# OTP5.net
KiCad netlist of a schematic drawn in Altium Designer
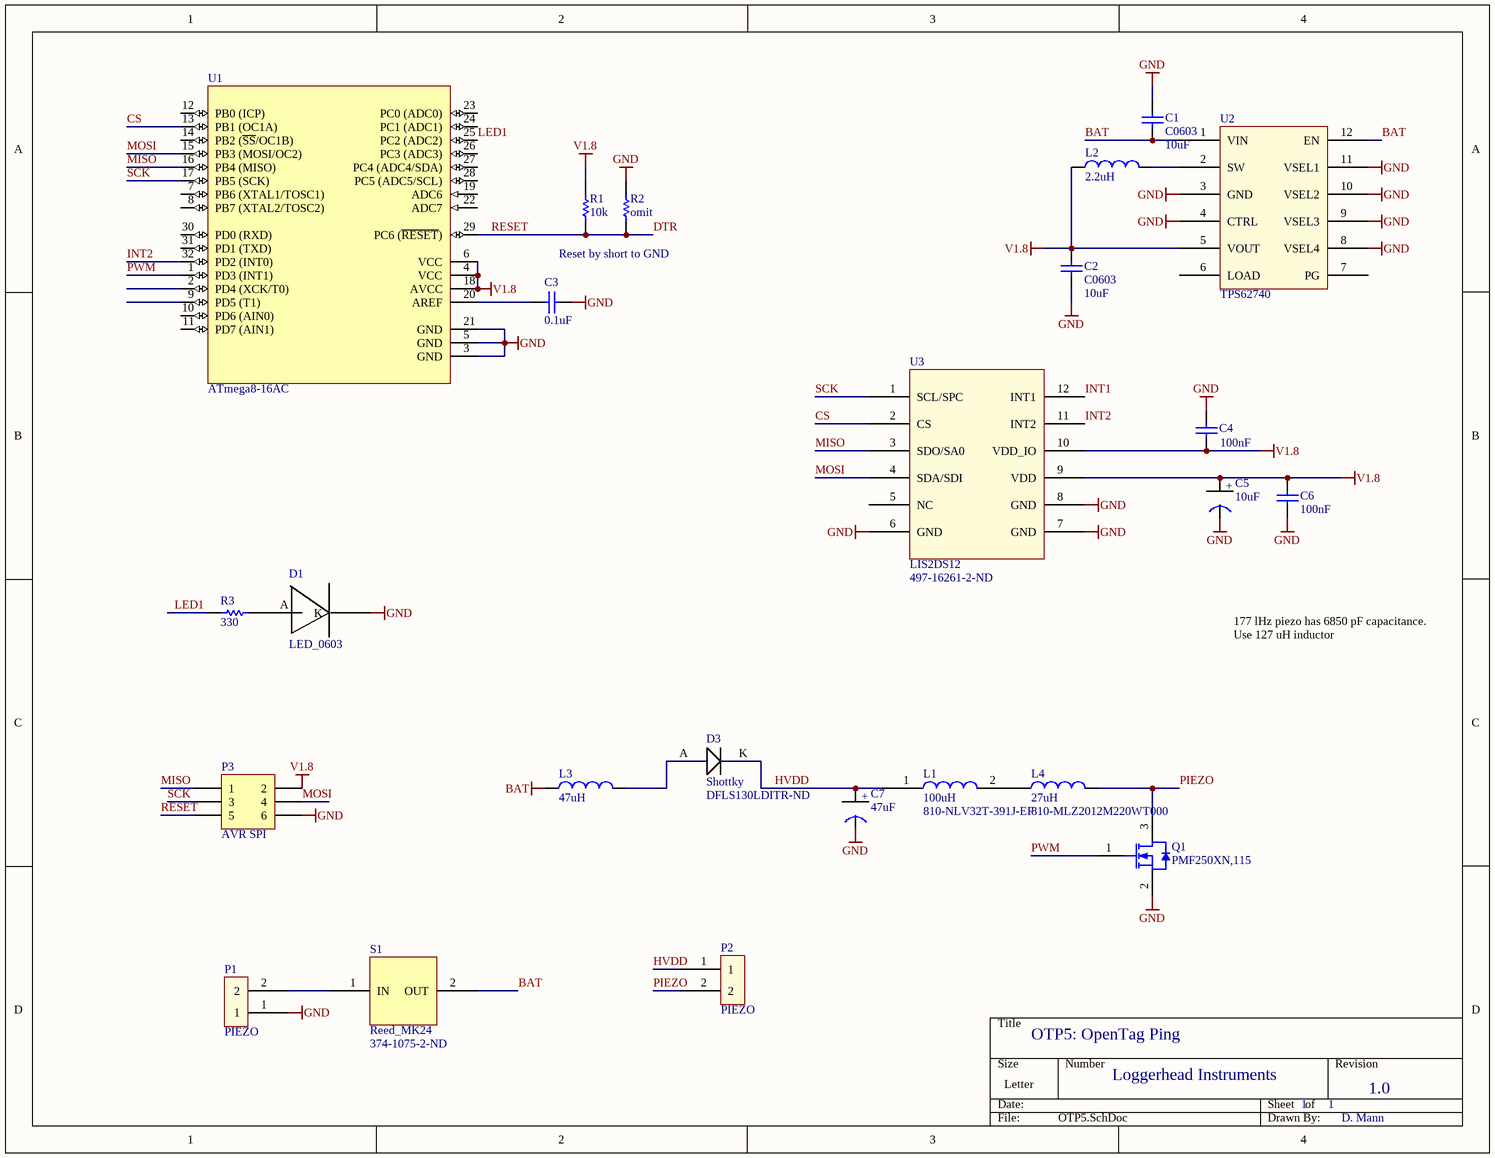
[diagram p0: OTP5.SchDoc]

(export (version "E")
  (design (tool "Eeschema 10.0.6"))
  (components
    (comp (ref "C1")
      (value "C0603")
      (footprint "0603")
      (description "Ceramic Chip Capacitor - Standard")
      (fields (field (name "ALTIUM_VALUE") "10uF") (field (name "PUBLISHER") "Altium Limited"))
      (libsource (lib "KEMET Chip Capacitor") (part "C0603"))
    )
    (comp (ref "C2")
      (value "C0603")
      (footprint "0603")
      (description "Ceramic Chip Capacitor - Standard")
      (fields (field (name "ALTIUM_VALUE") "10uF") (field (name "PUBLISHER") "Altium Limited"))
      (libsource (lib "KEMET Chip Capacitor") (part "C0603"))
    )
    (comp (ref "C3")
      (value "0.1uF")
      (footprint "0402")
      (description "Ceramic Chip Capacitor - Standard")
      (fields (field (name "PUBLISHER") "Altium Limited"))
      (libsource (lib "KEMET Chip Capacitor") (part "C0402"))
    )
    (comp (ref "C4")
      (value "100nF")
      (footprint "0402")
      (description "Ceramic Chip Capacitor - Standard")
      (fields (field (name "PUBLISHER") "Altium Limited"))
      (libsource (lib "KEMET Chip Capacitor") (part "C0402"))
    )
    (comp (ref "C5") (value "10uF") (footprint "Tant0805") (libsource (lib "Loggerhead") (part "Tant0805")))
    (comp (ref "C6")
      (value "100nF")
      (footprint "0402")
      (description "Ceramic Chip Capacitor - Standard")
      (fields (field (name "PUBLISHER") "Altium Limited"))
      (libsource (lib "KEMET Chip Capacitor") (part "C0402"))
    )
    (comp (ref "C7") (value "47uF") (footprint "Tant0805") (libsource (lib "Loggerhead") (part "Tant0805")))
    (comp (ref "D1")
      (value "LED_0603")
      (footprint "Diode0603")
      (libsource (lib "Loggerhead") (part "LED_0603"))
    )
    (comp (ref "D3")
      (value "Shottky")
      (footprint "DFLS130")
      (fields (field (name "SUPPLIER PART NUMBER 1") "DFLS130LDITR-ND"))
      (libsource (lib "Loggerhead") (part "DFLS130"))
    )
    (comp (ref "L1")
      (value "100uH")
      (footprint "Inductor_NLV32T")
      (fields (field (name "SUPPLIER PART NUMBER 1") "810-NLV32T-391J-EF"))
      (libsource (lib "Loggerhead") (part "Inductor_NLV32T"))
    )
    (comp (ref "L2")
      (value "2.2uH")
      (footprint "Inductor KLZ1608AHR")
      (libsource (lib "Loggerhead") (part "Inductor KLZ1608"))
    )
    (comp (ref "L3")
      (value "47uH")
      (footprint "Inductor KLZ1608AHR")
      (libsource (lib "Loggerhead") (part "Inductor KLZ1608"))
    )
    (comp (ref "L4")
      (value "27uH")
      (footprint "Inductor MLZ2012M220WT000")
      (fields (field (name "SUPPLIER PART NUMBER 1") "810-MLZ2012M220WT000"))
      (libsource (lib "Loggerhead") (part "Inductor MLZ2012M220WT000"))
    )
    (comp (ref "P1") (value "PIEZO") (footprint "PIEZO") (libsource (lib "") (part "PIEZO_1")))
    (comp (ref "P2") (value "PIEZO") (footprint "PIEZO") (libsource (lib "Loggerhead") (part "PIEZO")))
    (comp (ref "P3")
      (value "AVR SPI")
      (footprint "HDR2X3")
      (description "Header, 3-Pin, Dual row")
      (fields (field (name "PUBLISHER") "Altium Limited"))
      (libsource (lib "Miscellaneous Connectors") (part "Header 3X2"))
    )
    (comp (ref "Q1")
      (value "PMF250XN,115")
      (footprint "NXP-SOT323_N")
      (description "N-Channel Trench MOSFET, 30 V, 0.9 A, -55 to 150 degC, 3-Pin SOT323, Tape and Reel")
      (fields (field (name "MANUFACTURER") "NXP Semiconductors"))
      (libsource (lib "NXP Semiconductors Standard MOSFETs") (part "PMF250XN,115"))
    )
    (comp (ref "R1")
      (value "10k")
      (footprint "2-0402")
      (fields (field (name "PUBLISHER") "Altium Limited"))
      (libsource (lib "Panasonic Resistor") (part "ERJ2RB"))
    )
    (comp (ref "R2")
      (value "omit")
      (footprint "3-0603")
      (fields (field (name "PUBLISHER") "Altium Limited"))
      (libsource (lib "Panasonic Resistor") (part "ERJ3RK"))
    )
    (comp (ref "R3")
      (value "330")
      (footprint "2-0402")
      (fields (field (name "PUBLISHER") "Altium Limited"))
      (libsource (lib "Panasonic Resistor") (part "ERJ2RB"))
    )
    (comp (ref "S1")
      (value "Reed_MK24")
      (footprint "Reed MK24-B-3")
      (fields (field (name "SUPPLIER PART NUMBER 1") "374-1075-2-ND"))
      (libsource (lib "Loggerhead") (part "Reed_MK24"))
    )
    (comp (ref "U1")
      (value "ATmega8-16AC")
      (footprint "32M1-A_M")
      (description "8-Bit AVR Microcontroller with 8K Bytes of In-System Programmable Flash Memory")
      (fields (field (name "PUBLISHER") "Altium Limited"))
      (libsource (lib "Atmel Microcontroller 8-Bit AVR") (part "ATmega8-16AC"))
    )
    (comp (ref "U2")
      (value "TPS62740")
      (footprint "TPS6274x")
      (libsource (lib "Loggerhead") (part "TPS6274x"))
    )
    (comp (ref "U3")
      (value "LIS2DS12")
      (footprint "LGA-12")
      (fields (field (name "SUPPLIER PART NUMBER 1") "497-16261-2-ND"))
      (libsource (lib "Loggerhead") (part "LIS2DS12"))
    )
  )
  (nets
    (net (code "1") (name "/CS") (class "Default")
      (node (ref "U1") (pin "13") (pinfunction "PB1_(OC1A)_13") (pintype "bidirectional"))
      (node (ref "U3") (pin "2") (pinfunction "CS_2") (pintype "passive"))
    )
    (net (code "2") (name "/DTR") (class "Default")
      (node (ref "P3") (pin "5") (pinfunction "5_5") (pintype "passive"))
      (node (ref "R1") (pin "1") (pinfunction "1_1") (pintype "passive"))
      (node (ref "R2") (pin "1") (pinfunction "1_1") (pintype "passive"))
      (node (ref "U1") (pin "29") (pinfunction "PC6_(~{RESET})_29") (pintype "bidirectional"))
    )
    (net (code "3") (name "/HVDD") (class "Default")
      (node (ref "C7") (pin "2") (pinfunction "+_2") (pintype "passive"))
      (node (ref "D3") (pin "K") (pintype "passive"))
      (node (ref "L1") (pin "1") (pinfunction "1_1") (pintype "passive"))
      (node (ref "P2") (pin "1") (pinfunction "1_1") (pintype "passive"))
    )
    (net (code "4") (name "/INT1") (class "Default")
      (node (ref "U3") (pin "12") (pinfunction "INT1_12") (pintype "passive"))
    )
    (net (code "5") (name "/INT2") (class "Default")
      (node (ref "U1") (pin "32") (pinfunction "PD2_(INT0)_32") (pintype "bidirectional"))
      (node (ref "U3") (pin "11") (pinfunction "INT2_11") (pintype "passive"))
    )
    (net (code "6") (name "/LED1") (class "Default")
      (node (ref "R3") (pin "2") (pinfunction "2_2") (pintype "passive"))
      (node (ref "U1") (pin "25") (pinfunction "PC2_(ADC2)_25") (pintype "bidirectional"))
    )
    (net (code "7") (name "/MISO") (class "Default")
      (node (ref "P3") (pin "1") (pinfunction "1_1") (pintype "passive"))
      (node (ref "U1") (pin "16") (pinfunction "PB4_(MISO)_16") (pintype "bidirectional"))
      (node (ref "U3") (pin "3") (pinfunction "SDO/SA0_3") (pintype "passive"))
    )
    (net (code "8") (name "/MOSI") (class "Default")
      (node (ref "P3") (pin "4") (pinfunction "4_4") (pintype "passive"))
      (node (ref "U1") (pin "15") (pinfunction "PB3_(MOSI/OC2)_15") (pintype "bidirectional"))
      (node (ref "U3") (pin "4") (pinfunction "SDA/SDI_4") (pintype "passive"))
    )
    (net (code "9") (name "/PIEZO") (class "Default")
      (node (ref "L4") (pin "2") (pinfunction "2_2") (pintype "passive"))
      (node (ref "P2") (pin "2") (pinfunction "2_2") (pintype "passive"))
      (node (ref "Q1") (pin "3") (pinfunction "D_3") (pintype "passive"))
    )
    (net (code "10") (name "/PWM") (class "Default")
      (node (ref "Q1") (pin "1") (pinfunction "G_1") (pintype "passive"))
      (node (ref "U1") (pin "1") (pinfunction "PD3_(INT1)_1") (pintype "bidirectional"))
    )
    (net (code "11") (name "/SCK") (class "Default")
      (node (ref "P3") (pin "3") (pinfunction "3_3") (pintype "passive"))
      (node (ref "U1") (pin "17") (pinfunction "PB5_(SCK)_17") (pintype "bidirectional"))
      (node (ref "U3") (pin "1") (pinfunction "SCL/SPC_1") (pintype "passive"))
    )
    (net (code "12") (name "BAT") (class "Default")
      (node (ref "C1") (pin "1") (pinfunction "1_1") (pintype "passive"))
      (node (ref "L3") (pin "1") (pinfunction "1_1") (pintype "passive"))
      (node (ref "S1") (pin "2") (pinfunction "OUT_2") (pintype "passive"))
      (node (ref "U2") (pin "1") (pinfunction "VIN_1") (pintype "passive"))
      (node (ref "U2") (pin "12") (pinfunction "EN_12") (pintype "passive"))
    )
    (net (code "13") (name "GND") (class "Default")
      (node (ref "C1") (pin "2") (pinfunction "2_2") (pintype "passive"))
      (node (ref "C2") (pin "1") (pinfunction "1_1") (pintype "passive"))
      (node (ref "C3") (pin "2") (pinfunction "2_2") (pintype "passive"))
      (node (ref "C4") (pin "2") (pinfunction "2_2") (pintype "passive"))
      (node (ref "C5") (pin "1") (pinfunction "GND_1") (pintype "passive"))
      (node (ref "C6") (pin "2") (pinfunction "2_2") (pintype "passive"))
      (node (ref "C7") (pin "1") (pinfunction "GND_1") (pintype "passive"))
      (node (ref "D1") (pin "K") (pinfunction "K_K") (pintype "passive"))
      (node (ref "P1") (pin "1") (pinfunction "1_1") (pintype "passive"))
      (node (ref "P3") (pin "6") (pinfunction "6_6") (pintype "passive"))
      (node (ref "Q1") (pin "2") (pinfunction "S_2") (pintype "passive"))
      (node (ref "R2") (pin "2") (pinfunction "2_2") (pintype "passive"))
      (node (ref "U1") (pin "21") (pinfunction "GND_21") (pintype "power_in"))
      (node (ref "U1") (pin "3") (pinfunction "GND_3") (pintype "power_in"))
      (node (ref "U1") (pin "5") (pinfunction "GND_5") (pintype "power_in"))
      (node (ref "U2") (pin "10") (pinfunction "VSEL2_10") (pintype "passive"))
      (node (ref "U2") (pin "11") (pinfunction "VSEL1_11") (pintype "passive"))
      (node (ref "U2") (pin "3") (pinfunction "GND_3") (pintype "passive"))
      (node (ref "U2") (pin "4") (pinfunction "CTRL_4") (pintype "passive"))
      (node (ref "U2") (pin "8") (pinfunction "VSEL4_8") (pintype "passive"))
      (node (ref "U2") (pin "9") (pinfunction "VSEL3_9") (pintype "passive"))
      (node (ref "U3") (pin "6") (pinfunction "GND_6") (pintype "passive"))
      (node (ref "U3") (pin "7") (pinfunction "GND_7") (pintype "passive"))
      (node (ref "U3") (pin "8") (pinfunction "GND_8") (pintype "passive"))
    )
    (net (code "14") (name "Net-(D1-PadA)") (class "Default")
      (node (ref "D1") (pin "A") (pinfunction "A_A") (pintype "passive"))
      (node (ref "R3") (pin "1") (pinfunction "1_1") (pintype "passive"))
    )
    (net (code "15") (name "Net-(D3-PadA)") (class "Default")
      (node (ref "D3") (pin "A") (pintype "passive"))
      (node (ref "L3") (pin "2") (pinfunction "2_2") (pintype "passive"))
    )
    (net (code "16") (name "Net-(L1-Pad2)") (class "Default")
      (node (ref "L1") (pin "2") (pinfunction "2_2") (pintype "passive"))
      (node (ref "L4") (pin "1") (pinfunction "1_1") (pintype "passive"))
    )
    (net (code "17") (name "Net-(S1-IN)") (class "Default")
      (node (ref "P1") (pin "2") (pinfunction "2_2") (pintype "passive"))
      (node (ref "S1") (pin "1") (pinfunction "IN_1") (pintype "passive"))
    )
    (net (code "18") (name "Net-(U1-AREF)") (class "Default")
      (node (ref "C3") (pin "1") (pinfunction "1_1") (pintype "passive"))
      (node (ref "U1") (pin "20") (pinfunction "AREF_20") (pintype "passive"))
    )
    (net (code "19") (name "Net-(U2-SW)") (class "Default")
      (node (ref "L2") (pin "2") (pinfunction "2_2") (pintype "passive"))
      (node (ref "U2") (pin "2") (pinfunction "SW_2") (pintype "passive"))
    )
    (net (code "20") (name "V1.8") (class "Default")
      (node (ref "C2") (pin "2") (pinfunction "2_2") (pintype "passive"))
      (node (ref "C4") (pin "1") (pinfunction "1_1") (pintype "passive"))
      (node (ref "C5") (pin "2") (pinfunction "+_2") (pintype "passive"))
      (node (ref "C6") (pin "1") (pinfunction "1_1") (pintype "passive"))
      (node (ref "L2") (pin "1") (pinfunction "1_1") (pintype "passive"))
      (node (ref "P3") (pin "2") (pinfunction "2_2") (pintype "passive"))
      (node (ref "R1") (pin "2") (pinfunction "2_2") (pintype "passive"))
      (node (ref "U1") (pin "18") (pinfunction "AVCC_18") (pintype "power_in"))
      (node (ref "U1") (pin "4") (pinfunction "VCC_4") (pintype "power_in"))
      (node (ref "U1") (pin "6") (pinfunction "VCC_6") (pintype "power_in"))
      (node (ref "U2") (pin "5") (pinfunction "VOUT_5") (pintype "passive"))
      (node (ref "U3") (pin "10") (pinfunction "VDD_IO_10") (pintype "passive"))
      (node (ref "U3") (pin "9") (pinfunction "VDD_9") (pintype "passive"))
    )
    (net (code "21") (name "unconnected-(U1-ADC6-Pad19)") (class "Default")
      (node (ref "U1") (pin "19") (pinfunction "ADC6_19") (pintype "input"))
    )
    (net (code "22") (name "unconnected-(U1-ADC7-Pad22)") (class "Default")
      (node (ref "U1") (pin "22") (pinfunction "ADC7_22") (pintype "input"))
    )
    (net (code "23") (name "unconnected-(U1-PB0_(ICP)-Pad12)") (class "Default")
      (node (ref "U1") (pin "12") (pinfunction "PB0_(ICP)_12") (pintype "bidirectional"))
    )
    (net (code "24") (name "unconnected-(U1-PB2_(~{SS}{slash}OC1B)-Pad14)") (class "Default")
      (node (ref "U1") (pin "14") (pinfunction "PB2_(~{SS}/OC1B)_14") (pintype "bidirectional"))
    )
    (net (code "25") (name "unconnected-(U1-PB6_(XTAL1{slash}TOSC1)-Pad7)") (class "Default")
      (node (ref "U1") (pin "7") (pinfunction "PB6_(XTAL1/TOSC1)_7") (pintype "bidirectional"))
    )
    (net (code "26") (name "unconnected-(U1-PB7_(XTAL2{slash}TOSC2)-Pad8)") (class "Default")
      (node (ref "U1") (pin "8") (pinfunction "PB7_(XTAL2/TOSC2)_8") (pintype "bidirectional"))
    )
    (net (code "27") (name "unconnected-(U1-PC0_(ADC0)-Pad23)") (class "Default")
      (node (ref "U1") (pin "23") (pinfunction "PC0_(ADC0)_23") (pintype "bidirectional"))
    )
    (net (code "28") (name "unconnected-(U1-PC1_(ADC1)-Pad24)") (class "Default")
      (node (ref "U1") (pin "24") (pinfunction "PC1_(ADC1)_24") (pintype "bidirectional"))
    )
    (net (code "29") (name "unconnected-(U1-PC3_(ADC3)-Pad26)") (class "Default")
      (node (ref "U1") (pin "26") (pinfunction "PC3_(ADC3)_26") (pintype "bidirectional"))
    )
    (net (code "30") (name "unconnected-(U1-PC4_(ADC4{slash}SDA)-Pad27)") (class "Default")
      (node (ref "U1") (pin "27") (pinfunction "PC4_(ADC4/SDA)_27") (pintype "bidirectional"))
    )
    (net (code "31") (name "unconnected-(U1-PC5_(ADC5{slash}SCL)-Pad28)") (class "Default")
      (node (ref "U1") (pin "28") (pinfunction "PC5_(ADC5/SCL)_28") (pintype "bidirectional"))
    )
    (net (code "32") (name "unconnected-(U1-PD0_(RXD)-Pad30)") (class "Default")
      (node (ref "U1") (pin "30") (pinfunction "PD0_(RXD)_30") (pintype "bidirectional"))
    )
    (net (code "33") (name "unconnected-(U1-PD1_(TXD)-Pad31)") (class "Default")
      (node (ref "U1") (pin "31") (pinfunction "PD1_(TXD)_31") (pintype "bidirectional"))
    )
    (net (code "34") (name "unconnected-(U1-PD4_(XCK{slash}T0)-Pad2)") (class "Default")
      (node (ref "U1") (pin "2") (pinfunction "PD4_(XCK/T0)_2") (pintype "bidirectional"))
    )
    (net (code "35") (name "unconnected-(U1-PD5_(T1)-Pad9)") (class "Default")
      (node (ref "U1") (pin "9") (pinfunction "PD5_(T1)_9") (pintype "bidirectional"))
    )
    (net (code "36") (name "unconnected-(U1-PD6_(AIN0)-Pad10)") (class "Default")
      (node (ref "U1") (pin "10") (pinfunction "PD6_(AIN0)_10") (pintype "bidirectional"))
    )
    (net (code "37") (name "unconnected-(U1-PD7_(AIN1)-Pad11)") (class "Default")
      (node (ref "U1") (pin "11") (pinfunction "PD7_(AIN1)_11") (pintype "bidirectional"))
    )
    (net (code "38") (name "unconnected-(U2-LOAD-Pad6)") (class "Default")
      (node (ref "U2") (pin "6") (pinfunction "LOAD_6") (pintype "passive"))
    )
    (net (code "39") (name "unconnected-(U2-PG-Pad7)") (class "Default")
      (node (ref "U2") (pin "7") (pinfunction "PG_7") (pintype "passive"))
    )
    (net (code "40") (name "unconnected-(U3-NC-Pad5)") (class "Default")
      (node (ref "U3") (pin "5") (pinfunction "NC_5") (pintype "passive"))
    )
  )
)
